# Control.net
KiCad netlist of a schematic drawn in Altium Designer
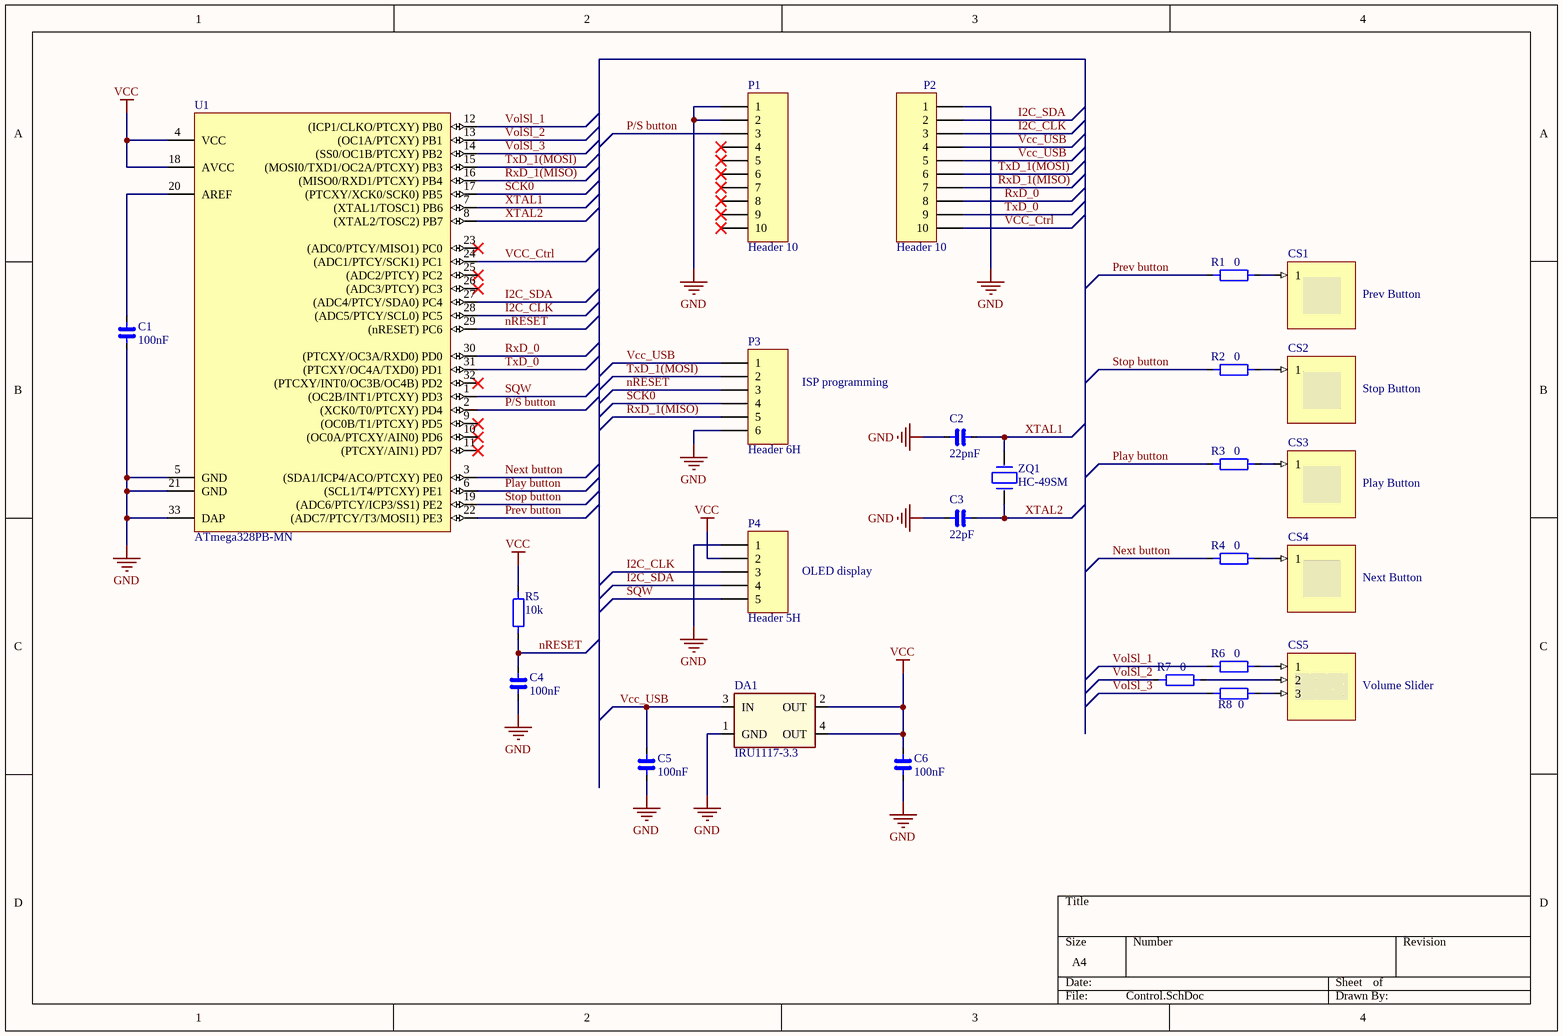
[diagram p0: Control.SchDoc]

(export (version "E")
  (design (tool "Eeschema 10.0.6"))
  (components
    (comp (ref "C1")
      (value "100nF")
      (footprint "SM/C_0603")
      (fields
        (field (name "VOLTAGE") "50V")
        (field (name "MANUFACTURER") "AVX")
        (field (name "TOLERANCE") "±20%")
      )
      (libsource (lib "MyLib") (part "C_0603"))
    )
    (comp (ref "C2")
      (value "22pnF")
      (footprint "SM/C_0603")
      (fields
        (field (name "VOLTAGE") "50V")
        (field (name "MANUFACTURER") "AVX")
        (field (name "TOLERANCE") "±20%")
      )
      (libsource (lib "MyLib") (part "C_0603"))
    )
    (comp (ref "C3")
      (value "22pF")
      (footprint "SM/C_0603")
      (fields
        (field (name "VOLTAGE") "50V")
        (field (name "MANUFACTURER") "AVX")
        (field (name "TOLERANCE") "±20%")
      )
      (libsource (lib "MyLib") (part "C_0603"))
    )
    (comp (ref "C4")
      (value "100nF")
      (footprint "SM/C_0603")
      (fields
        (field (name "VOLTAGE") "50V")
        (field (name "MANUFACTURER") "AVX")
        (field (name "TOLERANCE") "±20%")
      )
      (libsource (lib "MyLib") (part "C_0603"))
    )
    (comp (ref "C5")
      (value "100nF")
      (footprint "SM/C_0603")
      (fields
        (field (name "VOLTAGE") "50V")
        (field (name "MANUFACTURER") "AVX")
        (field (name "TOLERANCE") "±20%")
      )
      (libsource (lib "MyLib") (part "C_0603"))
    )
    (comp (ref "C6")
      (value "100nF")
      (footprint "SM/C_0603")
      (fields
        (field (name "VOLTAGE") "50V")
        (field (name "MANUFACTURER") "AVX")
        (field (name "TOLERANCE") "±20%")
      )
      (libsource (lib "MyLib") (part "C_0603"))
    )
    (comp (ref "CS1")
      (value "Prev Button")
      (description "QTouch Button")
      (libsource (lib "Control") (part "QTouchButton"))
    )
    (comp (ref "CS2")
      (value "Stop Button")
      (description "QTouch Button")
      (libsource (lib "Control") (part "QTouchButton"))
    )
    (comp (ref "CS3")
      (value "Play Button")
      (description "QTouch Button")
      (libsource (lib "Control") (part "QTouchButton"))
    )
    (comp (ref "CS4")
      (value "Next Button")
      (description "QTouch Button")
      (libsource (lib "Control") (part "QTouchButton"))
    )
    (comp (ref "CS5")
      (value "Volume Slider")
      (description "Medium QTouch Slider")
      (libsource (lib "Control") (part "MediumQTouchSlider"))
    )
    (comp (ref "DA1") (value "IRU1117-3.3") (footprint "SOT223") (libsource (lib "MyLib") (part "IRU1117")))
    (comp (ref "P1")
      (value "Header 10")
      (footprint "HDR1X10")
      (description "Header, 10-Pin")
      (fields (field (name "PUBLISHER") "Altium Limited"))
      (libsource (lib "") (part "Header 10_1"))
    )
    (comp (ref "P2")
      (value "Header 10")
      (footprint "HDR1X10")
      (description "Header, 10-Pin")
      (fields (field (name "PUBLISHER") "Altium Limited"))
      (libsource (lib "Miscellaneous Connectors") (part "Header 10"))
    )
    (comp (ref "P3")
      (value "Header 6H")
      (footprint "Header 6 SMD")
      (description "Header, 5-Pin, Right Angle")
      (fields (field (name "PUBLISHER") "Altium Limited"))
      (libsource (lib "Control") (part "Header 6H"))
    )
    (comp (ref "P4")
      (value "Header 5H")
      (footprint "Header 5 SMD")
      (description "Header, 5-Pin, Right Angle")
      (fields (field (name "PUBLISHER") "Altium Limited"))
      (libsource (lib "Control") (part "Header 5H"))
    )
    (comp (ref "R1")
      (value "0")
      (footprint "SM/R_0603")
      (fields
        (field (name "TOLERANCE") "±5%")
        (field (name "MANUFACTURER") "YAGEO")
        (field (name "POWER") "1/10W")
      )
      (libsource (lib "MyLib") (part "R_0603"))
    )
    (comp (ref "R2")
      (value "0")
      (footprint "SM/R_0603")
      (fields
        (field (name "TOLERANCE") "±5%")
        (field (name "MANUFACTURER") "YAGEO")
        (field (name "POWER") "1/10W")
      )
      (libsource (lib "MyLib") (part "R_0603"))
    )
    (comp (ref "R3")
      (value "0")
      (footprint "SM/R_0603")
      (fields
        (field (name "TOLERANCE") "±5%")
        (field (name "MANUFACTURER") "YAGEO")
        (field (name "POWER") "1/10W")
      )
      (libsource (lib "MyLib") (part "R_0603"))
    )
    (comp (ref "R4")
      (value "0")
      (footprint "SM/R_0603")
      (fields
        (field (name "TOLERANCE") "±5%")
        (field (name "MANUFACTURER") "YAGEO")
        (field (name "POWER") "1/10W")
      )
      (libsource (lib "MyLib") (part "R_0603"))
    )
    (comp (ref "R5")
      (value "10k")
      (footprint "SM/R_0603")
      (fields
        (field (name "TOLERANCE") "±5%")
        (field (name "MANUFACTURER") "YAGEO")
        (field (name "POWER") "1/10W")
      )
      (libsource (lib "MyLib") (part "R_0603"))
    )
    (comp (ref "R6")
      (value "0")
      (footprint "SM/R_0603")
      (fields
        (field (name "TOLERANCE") "±5%")
        (field (name "MANUFACTURER") "YAGEO")
        (field (name "POWER") "1/10W")
      )
      (libsource (lib "MyLib") (part "R_0603"))
    )
    (comp (ref "R7")
      (value "0")
      (footprint "SM/R_0603")
      (fields
        (field (name "TOLERANCE") "±5%")
        (field (name "MANUFACTURER") "YAGEO")
        (field (name "POWER") "1/10W")
      )
      (libsource (lib "MyLib") (part "R_0603"))
    )
    (comp (ref "R8")
      (value "0")
      (footprint "SM/R_0603")
      (fields
        (field (name "TOLERANCE") "±5%")
        (field (name "MANUFACTURER") "YAGEO")
        (field (name "POWER") "1/10W")
      )
      (libsource (lib "MyLib") (part "R_0603"))
    )
    (comp (ref "U1")
      (value "ATmega328PB-MN")
      (footprint "32M1-A_N")
      (libsource (lib "Control") (part "ATmega328P-MN"))
    )
    (comp (ref "ZQ1") (value "HC-49SM") (footprint "HC-49SM") (libsource (lib "Control") (part "HC-49SM")))
  )
  (nets
    (net (code "1") (name "/I2C_CLK") (class "Default")
      (node (ref "P2") (pin "3") (pinfunction "3_3") (pintype "passive"))
      (node (ref "P4") (pin "3") (pinfunction "3_3") (pintype "passive"))
      (node (ref "U1") (pin "28") (pinfunction "(ADC5/PTCY/SCL0)_PC5_28") (pintype "bidirectional"))
    )
    (net (code "2") (name "/I2C_SDA") (class "Default")
      (node (ref "P2") (pin "2") (pinfunction "2_2") (pintype "passive"))
      (node (ref "P4") (pin "4") (pinfunction "4_4") (pintype "passive"))
      (node (ref "U1") (pin "27") (pinfunction "(ADC4/PTCY/SDA0)_PC4_27") (pintype "bidirectional"))
    )
    (net (code "3") (name "/Next button") (class "Default")
      (node (ref "R4") (pin "1") (pinfunction "1_1") (pintype "passive"))
      (node (ref "U1") (pin "3") (pinfunction "(SDA1/ICP4/ACO/PTCXY)_PE0_3") (pintype "bidirectional"))
    )
    (net (code "4") (name "/Play button") (class "Default")
      (node (ref "R3") (pin "1") (pinfunction "1_1") (pintype "passive"))
      (node (ref "U1") (pin "6") (pinfunction "(SCL1/T4/PTCXY)_PE1_6") (pintype "bidirectional"))
    )
    (net (code "5") (name "/Prev button") (class "Default")
      (node (ref "R1") (pin "1") (pinfunction "1_1") (pintype "passive"))
      (node (ref "U1") (pin "22") (pinfunction "(ADC7/PTCY/T3/MOSI1)_PE3_22") (pintype "bidirectional"))
    )
    (net (code "6") (name "/P{slash}S button") (class "Default")
      (node (ref "P1") (pin "3") (pinfunction "3_3") (pintype "passive"))
      (node (ref "U1") (pin "2") (pinfunction "(XCK0/T0/PTCXY)_PD4_2") (pintype "bidirectional"))
    )
    (net (code "7") (name "/RxD_0") (class "Default")
      (node (ref "P2") (pin "8") (pinfunction "8_8") (pintype "passive"))
      (node (ref "U1") (pin "30") (pinfunction "(PTCXY/OC3A/RXD0)_PD0_30") (pintype "bidirectional"))
    )
    (net (code "8") (name "/RxD_1(MISO)") (class "Default")
      (node (ref "P2") (pin "7") (pinfunction "7_7") (pintype "passive"))
      (node (ref "P3") (pin "5") (pinfunction "5_5") (pintype "passive"))
      (node (ref "U1") (pin "16") (pinfunction "(MISO0/RXD1/PTCXY)_PB4_16") (pintype "bidirectional"))
    )
    (net (code "9") (name "/SCK0") (class "Default")
      (node (ref "P3") (pin "4") (pinfunction "4_4") (pintype "passive"))
      (node (ref "U1") (pin "17") (pinfunction "(PTCXY/XCK0/SCK0)_PB5_17") (pintype "bidirectional"))
    )
    (net (code "10") (name "/SQW") (class "Default")
      (node (ref "P4") (pin "5") (pinfunction "5_5") (pintype "passive"))
      (node (ref "U1") (pin "1") (pinfunction "(OC2B/INT1/PTCXY)_PD3_1") (pintype "bidirectional"))
    )
    (net (code "11") (name "/Stop button") (class "Default")
      (node (ref "R2") (pin "1") (pinfunction "1_1") (pintype "passive"))
      (node (ref "U1") (pin "19") (pinfunction "(ADC6/PTCY/ICP3/SS1)_PE2_19") (pintype "bidirectional"))
    )
    (net (code "12") (name "/TxD_0") (class "Default")
      (node (ref "P2") (pin "9") (pinfunction "9_9") (pintype "passive"))
      (node (ref "U1") (pin "31") (pinfunction "(PTCXY/OC4A/TXD0)_PD1_31") (pintype "bidirectional"))
    )
    (net (code "13") (name "/TxD_1(MOSI)") (class "Default")
      (node (ref "P2") (pin "6") (pinfunction "6_6") (pintype "passive"))
      (node (ref "P3") (pin "2") (pinfunction "2_2") (pintype "passive"))
      (node (ref "U1") (pin "15") (pinfunction "(MOSI0/TXD1/OC2A/PTCXY)_PB3_15") (pintype "bidirectional"))
    )
    (net (code "14") (name "/VCC_Ctrl") (class "Default")
      (node (ref "P2") (pin "10") (pinfunction "10_10") (pintype "passive"))
      (node (ref "U1") (pin "24") (pinfunction "(ADC1/PTCY/SCK1)_PC1_24") (pintype "bidirectional"))
    )
    (net (code "15") (name "/Vcc_USB") (class "Default")
      (node (ref "C5") (pin "1") (pinfunction "1_1") (pintype "passive"))
      (node (ref "DA1") (pin "3") (pinfunction "IN_3") (pintype "passive"))
      (node (ref "P2") (pin "4") (pinfunction "4_4") (pintype "passive"))
      (node (ref "P2") (pin "5") (pinfunction "5_5") (pintype "passive"))
      (node (ref "P3") (pin "1") (pinfunction "1_1") (pintype "passive"))
    )
    (net (code "16") (name "/VolSl_1") (class "Default")
      (node (ref "R6") (pin "1") (pinfunction "1_1") (pintype "passive"))
      (node (ref "U1") (pin "12") (pinfunction "(ICP1/CLKO/PTCXY)_PB0_12") (pintype "bidirectional"))
    )
    (net (code "17") (name "/VolSl_2") (class "Default")
      (node (ref "R7") (pin "1") (pinfunction "1_1") (pintype "passive"))
      (node (ref "U1") (pin "13") (pinfunction "(OC1A/PTCXY)_PB1_13") (pintype "bidirectional"))
    )
    (net (code "18") (name "/VolSl_3") (class "Default")
      (node (ref "R8") (pin "1") (pinfunction "1_1") (pintype "passive"))
      (node (ref "U1") (pin "14") (pinfunction "(SS0/OC1B/PTCXY)_PB2_14") (pintype "bidirectional"))
    )
    (net (code "19") (name "/XTAL1") (class "Default")
      (node (ref "C2") (pin "2") (pinfunction "2_2") (pintype "passive"))
      (node (ref "U1") (pin "7") (pinfunction "(XTAL1/TOSC1)_PB6_7") (pintype "bidirectional"))
      (node (ref "ZQ1") (pin "2") (pinfunction "2_2") (pintype "passive"))
    )
    (net (code "20") (name "/XTAL2") (class "Default")
      (node (ref "C3") (pin "2") (pinfunction "2_2") (pintype "passive"))
      (node (ref "U1") (pin "8") (pinfunction "(XTAL2/TOSC2)_PB7_8") (pintype "bidirectional"))
      (node (ref "ZQ1") (pin "1") (pinfunction "1_1") (pintype "passive"))
    )
    (net (code "21") (name "/nRESET") (class "Default")
      (node (ref "C4") (pin "1") (pinfunction "1_1") (pintype "passive"))
      (node (ref "P3") (pin "3") (pinfunction "3_3") (pintype "passive"))
      (node (ref "R5") (pin "1") (pinfunction "1_1") (pintype "passive"))
      (node (ref "U1") (pin "29") (pinfunction "(nRESET)_PC6_29") (pintype "bidirectional"))
    )
    (net (code "22") (name "GND") (class "Default")
      (node (ref "C1") (pin "2") (pinfunction "2_2") (pintype "passive"))
      (node (ref "C2") (pin "1") (pinfunction "1_1") (pintype "passive"))
      (node (ref "C3") (pin "1") (pinfunction "1_1") (pintype "passive"))
      (node (ref "C4") (pin "2") (pinfunction "2_2") (pintype "passive"))
      (node (ref "C5") (pin "2") (pinfunction "2_2") (pintype "passive"))
      (node (ref "C6") (pin "2") (pinfunction "2_2") (pintype "passive"))
      (node (ref "DA1") (pin "1") (pinfunction "GND_1") (pintype "passive"))
      (node (ref "P1") (pin "1") (pinfunction "1_1") (pintype "passive"))
      (node (ref "P1") (pin "2") (pinfunction "2_2") (pintype "passive"))
      (node (ref "P2") (pin "1") (pinfunction "1_1") (pintype "passive"))
      (node (ref "P3") (pin "6") (pinfunction "6_6") (pintype "passive"))
      (node (ref "P4") (pin "1") (pinfunction "1_1") (pintype "passive"))
      (node (ref "U1") (pin "21") (pinfunction "GND_21") (pintype "power_in"))
      (node (ref "U1") (pin "33") (pinfunction "DAP_33") (pintype "power_in"))
      (node (ref "U1") (pin "5") (pinfunction "GND_5") (pintype "power_in"))
    )
    (net (code "23") (name "Net-(CS1-Pad1)") (class "Default")
      (node (ref "CS1") (pin "1") (pinfunction "1_1") (pintype "input"))
      (node (ref "R1") (pin "2") (pinfunction "2_2") (pintype "passive"))
    )
    (net (code "24") (name "Net-(CS2-Pad1)") (class "Default")
      (node (ref "CS2") (pin "1") (pinfunction "1_1") (pintype "input"))
      (node (ref "R2") (pin "2") (pinfunction "2_2") (pintype "passive"))
    )
    (net (code "25") (name "Net-(CS3-Pad1)") (class "Default")
      (node (ref "CS3") (pin "1") (pinfunction "1_1") (pintype "input"))
      (node (ref "R3") (pin "2") (pinfunction "2_2") (pintype "passive"))
    )
    (net (code "26") (name "Net-(CS4-Pad1)") (class "Default")
      (node (ref "CS4") (pin "1") (pinfunction "1_1") (pintype "input"))
      (node (ref "R4") (pin "2") (pinfunction "2_2") (pintype "passive"))
    )
    (net (code "27") (name "Net-(CS5-Pad1)") (class "Default")
      (node (ref "CS5") (pin "1") (pinfunction "1_1") (pintype "input"))
      (node (ref "R6") (pin "2") (pinfunction "2_2") (pintype "passive"))
    )
    (net (code "28") (name "Net-(CS5-Pad2)") (class "Default")
      (node (ref "CS5") (pin "2") (pinfunction "2_2") (pintype "input"))
      (node (ref "R7") (pin "2") (pinfunction "2_2") (pintype "passive"))
    )
    (net (code "29") (name "Net-(CS5-Pad3)") (class "Default")
      (node (ref "CS5") (pin "3") (pinfunction "3_3") (pintype "input"))
      (node (ref "R8") (pin "2") (pinfunction "2_2") (pintype "passive"))
    )
    (net (code "30") (name "Net-(U1-AREF)") (class "Default")
      (node (ref "C1") (pin "1") (pinfunction "1_1") (pintype "passive"))
      (node (ref "U1") (pin "20") (pinfunction "AREF_20") (pintype "passive"))
    )
    (net (code "31") (name "VCC") (class "Default")
      (node (ref "C6") (pin "1") (pinfunction "1_1") (pintype "passive"))
      (node (ref "DA1") (pin "2") (pinfunction "OUT_2") (pintype "passive"))
      (node (ref "DA1") (pin "4") (pinfunction "OUT_4") (pintype "passive"))
      (node (ref "P4") (pin "2") (pinfunction "2_2") (pintype "passive"))
      (node (ref "R5") (pin "2") (pinfunction "2_2") (pintype "passive"))
      (node (ref "U1") (pin "18") (pinfunction "AVCC_18") (pintype "power_in"))
      (node (ref "U1") (pin "4") (pinfunction "VCC_4") (pintype "power_in"))
    )
    (net (code "32") (name "unconnected-(P1-Pad4)") (class "Default")
      (node (ref "P1") (pin "4") (pinfunction "4_4") (pintype "passive+no_connect"))
    )
    (net (code "33") (name "unconnected-(P1-Pad5)") (class "Default")
      (node (ref "P1") (pin "5") (pinfunction "5_5") (pintype "passive+no_connect"))
    )
    (net (code "34") (name "unconnected-(P1-Pad6)") (class "Default")
      (node (ref "P1") (pin "6") (pinfunction "6_6") (pintype "passive+no_connect"))
    )
    (net (code "35") (name "unconnected-(P1-Pad7)") (class "Default")
      (node (ref "P1") (pin "7") (pinfunction "7_7") (pintype "passive+no_connect"))
    )
    (net (code "36") (name "unconnected-(P1-Pad8)") (class "Default")
      (node (ref "P1") (pin "8") (pinfunction "8_8") (pintype "passive+no_connect"))
    )
    (net (code "37") (name "unconnected-(P1-Pad9)") (class "Default")
      (node (ref "P1") (pin "9") (pinfunction "9_9") (pintype "passive+no_connect"))
    )
    (net (code "38") (name "unconnected-(P1-Pad10)") (class "Default")
      (node (ref "P1") (pin "10") (pinfunction "10_10") (pintype "passive+no_connect"))
    )
    (net (code "39") (name "unconnected-(U1-(ADC0{slash}PTCY{slash}MISO1)_PC0-Pad23)") (class "Default")
      (node (ref "U1") (pin "23") (pinfunction "(ADC0/PTCY/MISO1)_PC0_23") (pintype "bidirectional+no_connect"))
    )
    (net (code "40") (name "unconnected-(U1-(ADC2{slash}PTCY)_PC2-Pad25)") (class "Default")
      (node (ref "U1") (pin "25") (pinfunction "(ADC2/PTCY)_PC2_25") (pintype "bidirectional+no_connect"))
    )
    (net (code "41") (name "unconnected-(U1-(ADC3{slash}PTCY)_PC3-Pad26)") (class "Default")
      (node (ref "U1") (pin "26") (pinfunction "(ADC3/PTCY)_PC3_26") (pintype "bidirectional+no_connect"))
    )
    (net (code "42") (name "unconnected-(U1-(OC0A{slash}PTCXY{slash}AIN0)_PD6-Pad10)") (class "Default")
      (node (ref "U1") (pin "10") (pinfunction "(OC0A/PTCXY/AIN0)_PD6_10") (pintype "bidirectional+no_connect"))
    )
    (net (code "43") (name "unconnected-(U1-(OC0B{slash}T1{slash}PTCXY)_PD5-Pad9)") (class "Default")
      (node (ref "U1") (pin "9") (pinfunction "(OC0B/T1/PTCXY)_PD5_9") (pintype "bidirectional+no_connect"))
    )
    (net (code "44") (name "unconnected-(U1-(PTCXY{slash}AIN1)_PD7-Pad11)") (class "Default")
      (node (ref "U1") (pin "11") (pinfunction "(PTCXY/AIN1)_PD7_11") (pintype "bidirectional+no_connect"))
    )
    (net (code "45") (name "unconnected-(U1-(PTCXY{slash}INT0{slash}OC3B{slash}OC4B)_PD2-Pad32)") (class "Default")
      (node (ref "U1") (pin "32") (pinfunction "(PTCXY/INT0/OC3B/OC4B)_PD2_32") (pintype "bidirectional+no_connect"))
    )
  )
)
